# Detector.net
KiCad netlist of a schematic drawn in Altium Designer
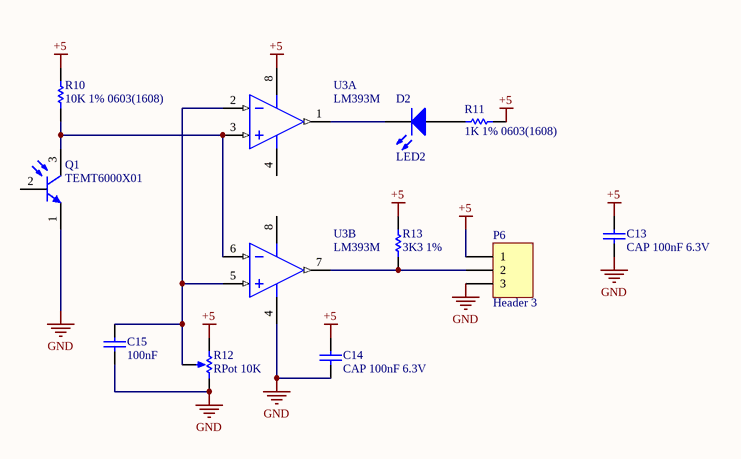
[diagram p0: Detector.SchDoc]

(export (version "E")
  (design (tool "Eeschema 10.0.6"))
  (components
    (comp (ref "C13")
      (value "CAP 100nF 6.3V")
      (footprint "CAPC0603(1608)100_N")
      (description "CAP 100nF 6.3V ±10% 0603 (1608 Metric) Thickness 1mm SMD")
      (fields (field (name "TOLERANCE") "Â±10%"))
      (libsource (lib "Altium Content Vault") (part "CAP"))
    )
    (comp (ref "C14")
      (value "CAP 100nF 6.3V")
      (footprint "CAPC0603(1608)100_N")
      (description "CAP 100nF 6.3V ±10% 0603 (1608 Metric) Thickness 1mm SMD")
      (fields (field (name "TOLERANCE") "Â±10%"))
      (libsource (lib "Altium Content Vault") (part "CAP"))
    )
    (comp (ref "C15")
      (value "100nF")
      (footprint "CAPC0603(1608)100_N")
      (description "CAP 100nF 6.3V ±10% 0603 (1608 Metric) Thickness 1mm SMD")
      (fields (field (name "TOLERANCE") "Â±10%"))
      (libsource (lib "Altium Content Vault") (part "CAP"))
    )
    (comp (ref "D2")
      (value "LED2")
      (footprint "0603")
      (description "Typical RED, GREEN, YELLOW, AMBER GaAs LED")
      (fields (field (name "PUBLISHER") "Altium Limited"))
      (libsource (lib "Miscellaneous Devices") (part "LED2"))
    )
    (comp (ref "P6")
      (value "Header 3")
      (footprint "PH2.0-WS-3P")
      (description "Header, 3-Pin")
      (fields (field (name "PUBLISHER") "Altium Limited"))
      (libsource (lib "Miscellaneous Connectors") (part "Header 3"))
    )
    (comp (ref "Q1")
      (value "TEMT6000X01")
      (footprint "VSIL-TEMT6000X01_V")
      (description "Ambient Light Sensor\r\n, 100 mW, -40 to 100 degC, 3-Pin SMD, RoHS, Tape and Reel")
      (libsource (lib "Altium Content Vault") (part "PHOTO-NPN-EBC-3"))
    )
    (comp (ref "R10")
      (value "10K 1% 0603(1608)")
      (footprint "RESC0603(1608)_N")
      (description "10K 0.1W 1% 0603 (1608 Metric)  SMD")
      (fields (field (name "POWER") "0.1 W") (field (name "TOLERANCE") "1 %"))
      (libsource (lib "Altium Content Vault") (part "RES"))
    )
    (comp (ref "R11")
      (value "1K 1% 0603(1608)")
      (footprint "RESC0603(1608)_N")
      (description "1K 0.1W 1% 0603 (1608 Metric)  SMD")
      (fields (field (name "TOLERANCE") "1 %") (field (name "POWER") "0.1 W"))
      (libsource (lib "Altium Content Vault") (part "RES"))
    )
    (comp (ref "R12")
      (value "RPot 10K")
      (footprint "BOUR-3362P")
      (description "Potentiometer")
      (fields (field (name "PUBLISHER") "Altium Limited"))
      (libsource (lib "MDR-36") (part "RPot"))
    )
    (comp (ref "R13")
      (value "3K3 1%")
      (footprint "RESC0603(1608)_N")
      (description "3K3 0.1W 1% 0603 (1608 Metric)  SMD")
      (fields (field (name "POWER") "0.1 W") (field (name "TOLERANCE") "1 %"))
      (libsource (lib "Altium Content Vault") (part "RES"))
    )
    (comp (ref "U3")
      (value "LM393M")
      (footprint "M08A_N")
      (description "Low Power Low Offset Voltage Dual Comparator, 8-pin Narrow SOIC")
      (fields (field (name "MANUFACTURER") "National Semiconductor"))
      (libsource (lib "Altium Content Vault") (part "AN-COMP-LM193-8"))
    )
  )
  (nets
    (net (code "1") (name "+5") (class "Default")
      (node (ref "C13") (pin "2") (pinfunction "2_2") (pintype "passive"))
      (node (ref "C14") (pin "2") (pinfunction "2_2") (pintype "passive"))
      (node (ref "P6") (pin "1") (pinfunction "1_1") (pintype "passive"))
      (node (ref "R10") (pin "2") (pinfunction "2_2") (pintype "passive"))
      (node (ref "R11") (pin "2") (pinfunction "2_2") (pintype "passive"))
      (node (ref "R12") (pin "1") (pinfunction "TOP_1") (pintype "passive"))
      (node (ref "R13") (pin "2") (pinfunction "2_2") (pintype "passive"))
      (node (ref "U3") (pin "8") (pinfunction "V+_8") (pintype "power_in"))
    )
    (net (code "2") (name "GND") (class "Default")
      (node (ref "C13") (pin "1") (pinfunction "1_1") (pintype "passive"))
      (node (ref "C14") (pin "1") (pinfunction "1_1") (pintype "passive"))
      (node (ref "C15") (pin "1") (pinfunction "1_1") (pintype "passive"))
      (node (ref "P6") (pin "3") (pinfunction "3_3") (pintype "passive"))
      (node (ref "Q1") (pin "1") (pinfunction "E_1") (pintype "passive"))
      (node (ref "R12") (pin "3") (pinfunction "BOT_3") (pintype "passive"))
      (node (ref "U3") (pin "4") (pinfunction "GND_4") (pintype "power_in"))
    )
    (net (code "3") (name "Net-(D2-A)") (class "Default")
      (node (ref "D2") (pin "1") (pinfunction "A_1") (pintype "passive"))
      (node (ref "R11") (pin "1") (pinfunction "1_1") (pintype "passive"))
    )
    (net (code "4") (name "Net-(D2-K)") (class "Default")
      (node (ref "D2") (pin "2") (pinfunction "K_2") (pintype "passive"))
      (node (ref "U3") (pin "1") (pinfunction "OUTA_1") (pintype "output"))
    )
    (net (code "5") (name "Net-(Q1-C)") (class "Default")
      (node (ref "Q1") (pin "3") (pinfunction "C_3") (pintype "passive"))
      (node (ref "R10") (pin "1") (pinfunction "1_1") (pintype "passive"))
      (node (ref "U3") (pin "3") (pinfunction "INA+_3") (pintype "input"))
      (node (ref "U3") (pin "6") (pinfunction "INB-_6") (pintype "input"))
    )
    (net (code "6") (name "Net-(R12-TAP)") (class "Default")
      (node (ref "C15") (pin "2") (pinfunction "2_2") (pintype "passive"))
      (node (ref "R12") (pin "2") (pinfunction "TAP_2") (pintype "passive"))
      (node (ref "U3") (pin "2") (pinfunction "INA-_2") (pintype "input"))
      (node (ref "U3") (pin "5") (pinfunction "INB+_5") (pintype "input"))
    )
    (net (code "7") (name "Net-(U3B-OUTB)") (class "Default")
      (node (ref "P6") (pin "2") (pinfunction "2_2") (pintype "passive"))
      (node (ref "R13") (pin "1") (pinfunction "1_1") (pintype "passive"))
      (node (ref "U3") (pin "7") (pinfunction "OUTB_7") (pintype "output"))
    )
    (net (code "8") (name "unconnected-(Q1-B-Pad2)") (class "Default")
      (node (ref "Q1") (pin "2") (pinfunction "B_2") (pintype "passive"))
    )
    (net (code "9") (name "unconnected-(U3A-GND-Pad4)") (class "Default")
      (node (ref "U3") (pin "4") (pinfunction "GND_4") (pintype "power_in"))
    )
    (net (code "10") (name "unconnected-(U3B-V+-Pad8)") (class "Default")
      (node (ref "U3") (pin "8") (pinfunction "V+_8") (pintype "power_in"))
    )
  )
)
